# Vapeix_mini_Shield.net
KiCad netlist of a schematic drawn in Altium Designer
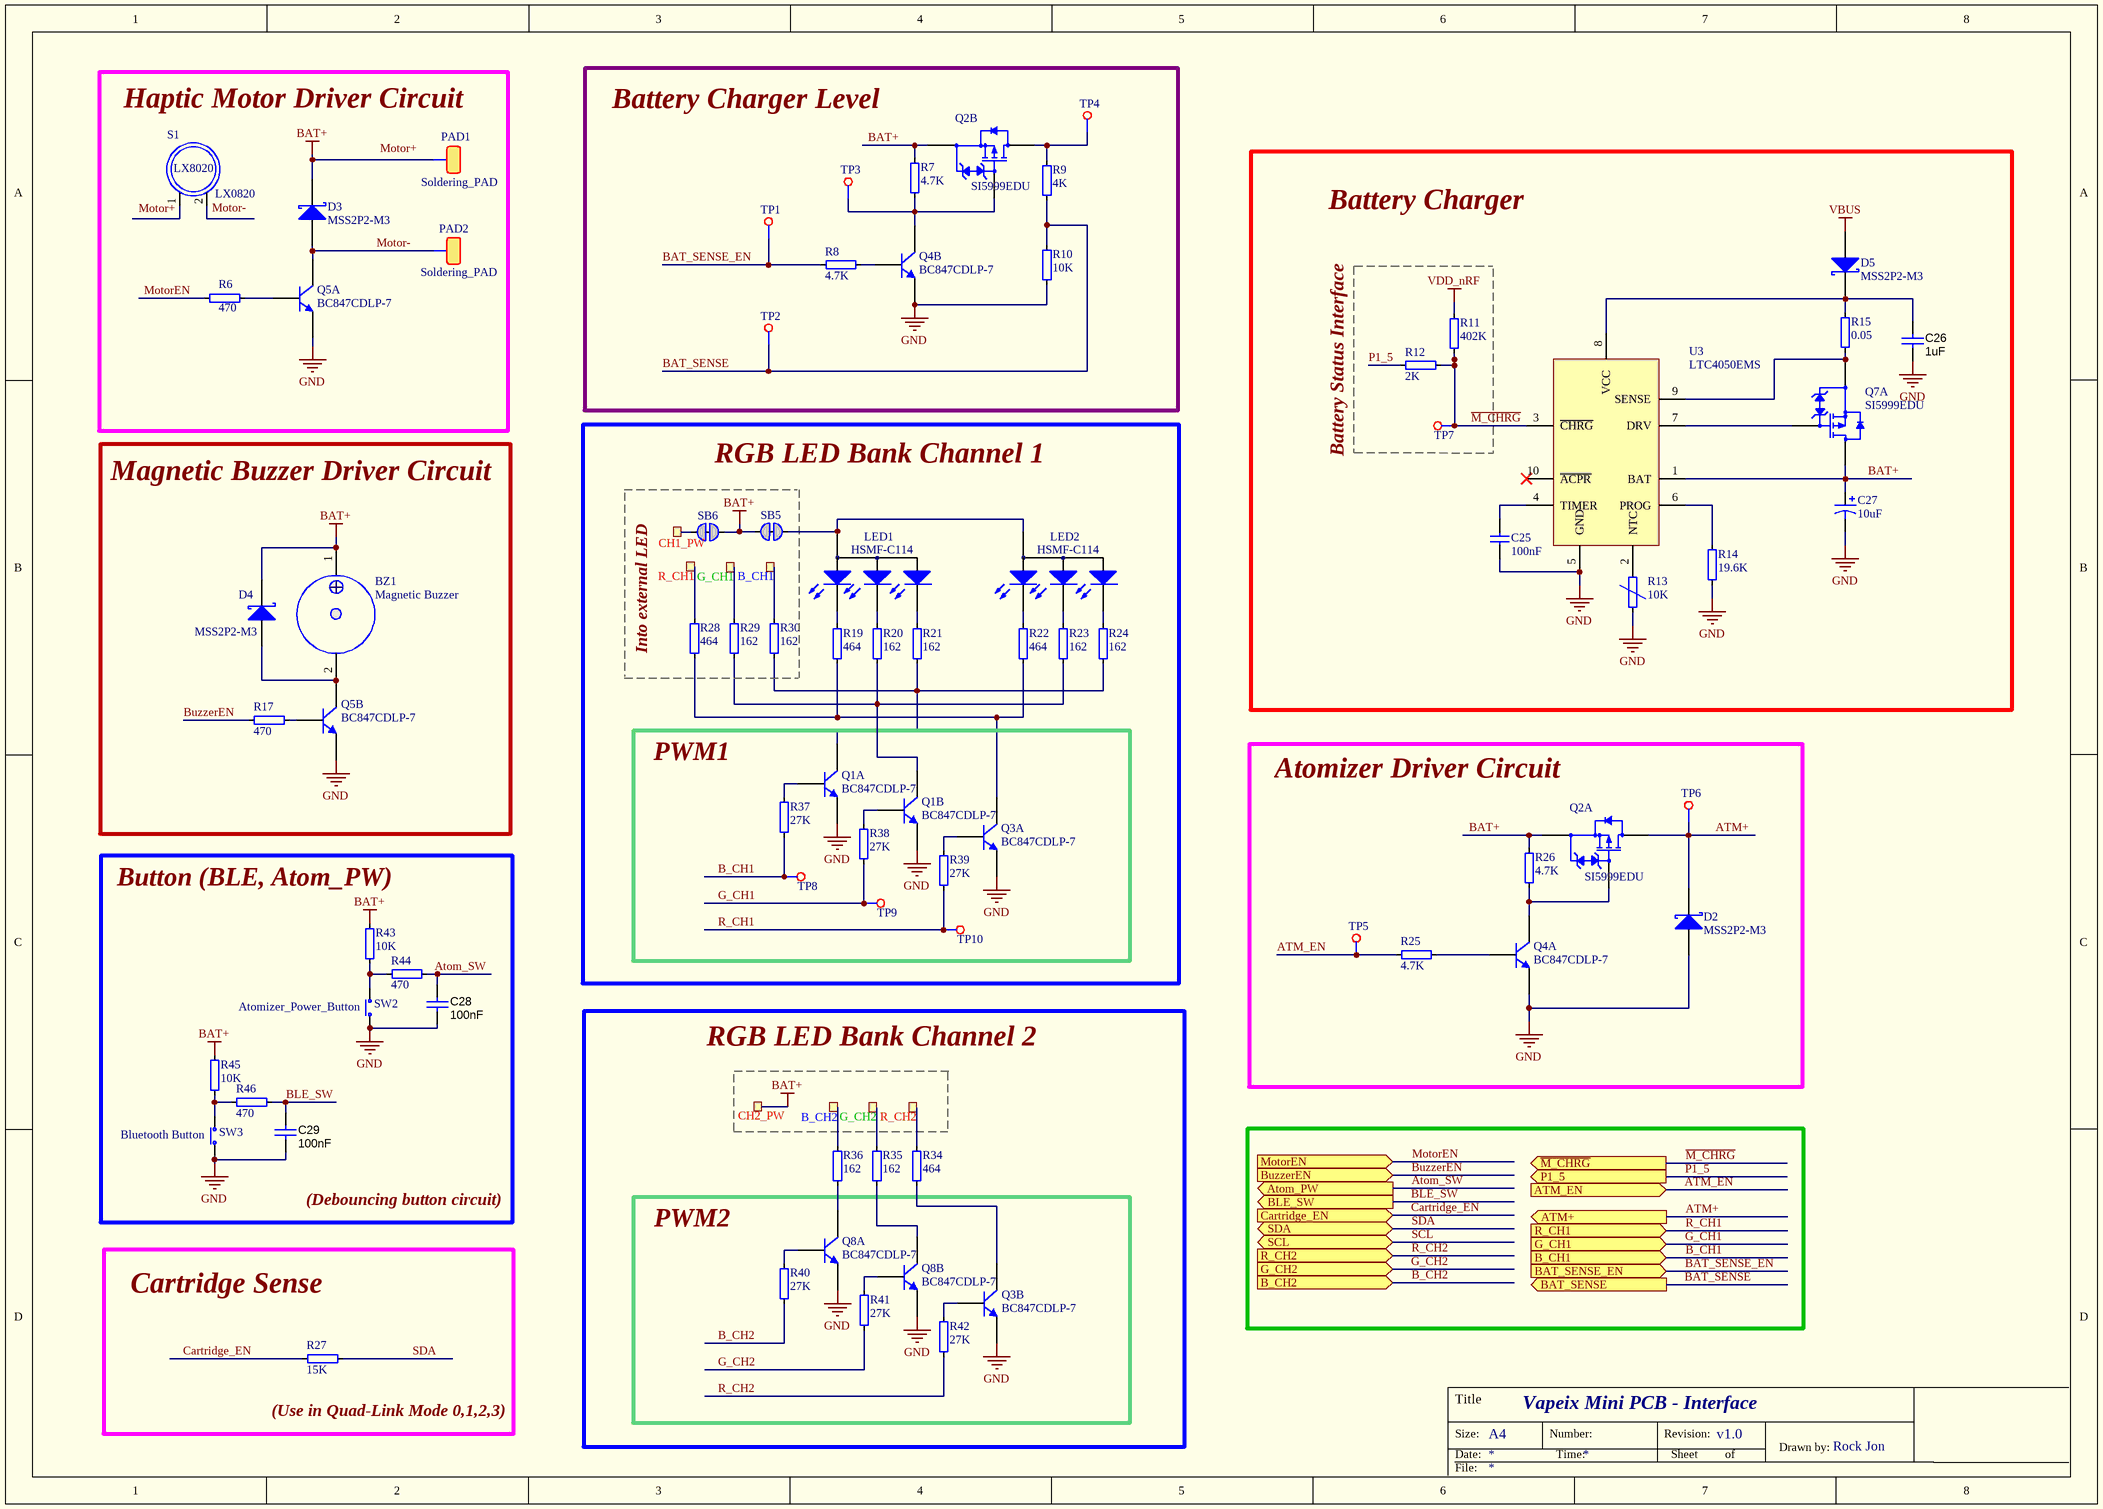
[diagram p0: Vapeix_mini_Shield.SchDoc]

(export (version "E")
  (design (tool "Eeschema 10.0.6"))
  (components
    (comp (ref "BZ1")
      (value "Magnetic Buzzer")
      (footprint "Magnetic Buzzer")
      (libsource (lib "VapeixS_LIB") (part "Magnetic Buzzer"))
    )
    (comp (ref "B_CH1")
      (value "TP")
      (footprint "TESTPAD-TH")
      (description "Testpoint, through hole")
      (fields (field (name "PART NUMBER") "Testpoint TH") (field (name "PUBLISHER") "Nordic Semiconductor"))
      (libsource (lib "pca10040") (part "TESTPAD_TH"))
    )
    (comp (ref "B_CH2")
      (value "TP")
      (footprint "TESTPAD-TH")
      (description "Testpoint, through hole")
      (fields (field (name "PART NUMBER") "Testpoint TH") (field (name "PUBLISHER") "Nordic Semiconductor"))
      (libsource (lib "pca10040") (part "TESTPAD_TH"))
    )
    (comp (ref "C25")
      (value "100nF")
      (footprint "C0201")
      (description "Capacitor, X7R, ±10%")
      (fields (field (name "PART NUMBER") "C0402-100n") (field (name "PUBLISHER") "Nordic Semiconductor"))
      (libsource (lib "Nordic Passive DB") (part "CAP"))
    )
    (comp (ref "C26")
      (value "~")
      (footprint "C0201")
      (description "CAP, CERM, 10 µF, 10 V, +/- 10%, X5R, 0805")
      (fields
        (field (name "PARTNUMBER") "GRM219R61A106KE44D")
        (field (name "VALUEDISPLAYED") "1uF")
        (field (name "MANUFACTURER") "MuRata")
        (field (name "PUBLISHER") "Texas Instruments")
      )
      (libsource (lib "Capacitor_Ceramic") (part "GRM219R61A106KE44D"))
    )
    (comp (ref "C27")
      (value "10uF")
      (footprint "CAPC1005X04L")
      (description "Polarized Capacitor (Surface Mount)")
      (fields (field (name "Comment") "Cap Pol3") (field (name "PUBLISHER") "Altium Limited"))
      (libsource (lib "Miscellaneous Devices") (part "Cap Pol3"))
    )
    (comp (ref "C28")
      (value "~")
      (footprint "C0201")
      (description "CAP, CERM, 10 µF, 10 V, +/- 10%, X5R, 0805")
      (fields
        (field (name "PARTNUMBER") "GRM219R61A106KE44D")
        (field (name "VALUEDISPLAYED") "100nF")
        (field (name "MANUFACTURER") "MuRata")
        (field (name "PUBLISHER") "Texas Instruments")
      )
      (libsource (lib "Capacitor_Ceramic") (part "GRM219R61A106KE44D"))
    )
    (comp (ref "C29")
      (value "~")
      (footprint "C0201")
      (description "CAP, CERM, 10 µF, 10 V, +/- 10%, X5R, 0805")
      (fields
        (field (name "PARTNUMBER") "GRM219R61A106KE44D")
        (field (name "VALUEDISPLAYED") "100nF")
        (field (name "MANUFACTURER") "MuRata")
        (field (name "PUBLISHER") "Texas Instruments")
      )
      (libsource (lib "Capacitor_Ceramic") (part "GRM219R61A106KE44D"))
    )
    (comp (ref "CH1_PW")
      (value "TP")
      (footprint "TESTPAD-TH")
      (description "Testpoint, through hole")
      (fields (field (name "PART NUMBER") "Testpoint TH") (field (name "PUBLISHER") "Nordic Semiconductor"))
      (libsource (lib "pca10040") (part "TESTPAD_TH"))
    )
    (comp (ref "CH2_PW")
      (value "TP")
      (footprint "TESTPAD-TH")
      (description "Testpoint, through hole")
      (fields (field (name "PART NUMBER") "Testpoint TH") (field (name "PUBLISHER") "Nordic Semiconductor"))
      (libsource (lib "pca10040") (part "TESTPAD_TH"))
    )
    (comp (ref "D2")
      (value "MSS2P2-M3")
      (footprint "MSS2P2-M3")
      (description "DIODE SCHOTTKY 20V 2A MICROSMP")
      (fields
        (field (name "MANUFACTURER") "Vishay Semiconductor Diodes Division")
        (field (name "MANUFACTURER PART NUMBER") "MSS2P2-M3/89A")
      )
      (libsource (lib "VapeixS_LIB") (part "MSS2P2-M3/89A"))
    )
    (comp (ref "D3")
      (value "MSS2P2-M3")
      (footprint "MSS2P2-M3")
      (description "DIODE SCHOTTKY 20V 2A MICROSMP")
      (fields
        (field (name "MANUFACTURER") "Vishay Semiconductor Diodes Division")
        (field (name "MANUFACTURER PART NUMBER") "MSS2P2-M3/89A")
      )
      (libsource (lib "VapeixS_LIB") (part "MSS2P2-M3/89A"))
    )
    (comp (ref "D4")
      (value "MSS2P2-M3")
      (footprint "MSS2P2-M3")
      (description "DIODE SCHOTTKY 20V 2A MICROSMP")
      (fields
        (field (name "MANUFACTURER") "Vishay Semiconductor Diodes Division")
        (field (name "MANUFACTURER PART NUMBER") "MSS2P2-M3/89A")
      )
      (libsource (lib "VapeixS_LIB") (part "MSS2P2-M3/89A"))
    )
    (comp (ref "D5")
      (value "MSS2P2-M3")
      (footprint "MSS2P2-M3")
      (description "DIODE SCHOTTKY 20V 2A MICROSMP")
      (fields
        (field (name "MANUFACTURER") "Vishay Semiconductor Diodes Division")
        (field (name "MANUFACTURER PART NUMBER") "MSS2P2-M3/89A")
      )
      (libsource (lib "VapeixS_LIB") (part "MSS2P2-M3/89A"))
    )
    (comp (ref "G_CH1")
      (value "TP")
      (footprint "TESTPAD-TH")
      (description "Testpoint, through hole")
      (fields (field (name "PART NUMBER") "Testpoint TH") (field (name "PUBLISHER") "Nordic Semiconductor"))
      (libsource (lib "pca10040") (part "TESTPAD_TH"))
    )
    (comp (ref "G_CH2")
      (value "TP")
      (footprint "TESTPAD-TH")
      (description "Testpoint, through hole")
      (fields (field (name "PART NUMBER") "Testpoint TH") (field (name "PUBLISHER") "Nordic Semiconductor"))
      (libsource (lib "pca10040") (part "TESTPAD_TH"))
    )
    (comp (ref "LED1")
      (value "HSMF-C114")
      (footprint "HSMF-C114")
      (description "LED RGB DIFFUSED 0606 SMD")
      (fields (field (name "MANUFACTURER") "Broadcom Limited"))
      (libsource (lib "VapeixS_LIB") (part "HSMF-C114"))
    )
    (comp (ref "LED2")
      (value "HSMF-C114")
      (footprint "HSMF-C114")
      (description "LED RGB DIFFUSED 0606 SMD")
      (fields (field (name "MANUFACTURER") "Broadcom Limited"))
      (libsource (lib "VapeixS_LIB") (part "HSMF-C114"))
    )
    (comp (ref "PAD1")
      (value "Soldering_PAD")
      (footprint "Soldering_PAD")
      (description "Soldering PAD")
      (libsource (lib "VapeixS_LIB") (part "Soldering_PAD"))
    )
    (comp (ref "PAD2")
      (value "Soldering_PAD")
      (footprint "Soldering_PAD")
      (description "Soldering PAD")
      (libsource (lib "VapeixS_LIB") (part "Soldering_PAD"))
    )
    (comp (ref "Q1")
      (value "BC847CDLP-7")
      (footprint "BC847CDLP-7")
      (description "TRANS 2NPN 45V 0.1A 6DFN")
      (fields (field (name "MANUFACTURER") "Diodes Incorporated"))
      (libsource (lib "") (part "BC847CDLP-7_1"))
    )
    (comp (ref "Q2")
      (value "SI5999EDU")
      (footprint "SI5999EDU")
      (description "MOSFET 2P-CH 20V 6A POWERPAK")
      (fields
        (field (name "MANUFACTURER") "Vishay Siliconix")
        (field (name "MANUFACTURER PART NUMBER") "SI5999EDU-T1-GE3")
      )
      (libsource (lib "") (part "SI5999EDU-T1-GE3_1"))
    )
    (comp (ref "Q3")
      (value "BC847CDLP-7")
      (footprint "BC847CDLP-7")
      (description "TRANS 2NPN 45V 0.1A 6DFN")
      (fields (field (name "MANUFACTURER") "Diodes Incorporated"))
      (libsource (lib "VapeixS_LIB") (part "BC847CDLP-7"))
    )
    (comp (ref "Q4")
      (value "BC847CDLP-7")
      (footprint "BC847CDLP-7")
      (description "TRANS 2NPN 45V 0.1A 6DFN")
      (fields (field (name "MANUFACTURER") "Diodes Incorporated"))
      (libsource (lib "") (part "BC847CDLP-7_2"))
    )
    (comp (ref "Q5")
      (value "BC847CDLP-7")
      (footprint "BC847CDLP-7")
      (description "TRANS 2NPN 45V 0.1A 6DFN")
      (fields (field (name "MANUFACTURER") "Diodes Incorporated"))
      (libsource (lib "") (part "BC847CDLP-7_1"))
    )
    (comp (ref "Q7")
      (value "SI5999EDU")
      (footprint "SI5999EDU")
      (description "MOSFET 2P-CH 20V 6A POWERPAK")
      (fields
        (field (name "MANUFACTURER") "Vishay Siliconix")
        (field (name "MANUFACTURER PART NUMBER") "SI5999EDU-T1-GE3")
      )
      (libsource (lib "VapeixS_LIB") (part "SI5999EDU-T1-GE3"))
    )
    (comp (ref "Q8")
      (value "BC847CDLP-7")
      (footprint "BC847CDLP-7")
      (description "TRANS 2NPN 45V 0.1A 6DFN")
      (fields (field (name "MANUFACTURER") "Diodes Incorporated"))
      (libsource (lib "VapeixS_LIB") (part "BC847CDLP-7"))
    )
    (comp (ref "R6")
      (value "470")
      (footprint "R0201")
      (description "Resistor, ±1%, 0.063W")
      (fields (field (name "PART NUMBER") "R0402-10k") (field (name "PUBLISHER") "Nordic Semiconductor"))
      (libsource (lib "Nordic Passive DB") (part "RES_1"))
    )
    (comp (ref "R7")
      (value "4.7K")
      (footprint "R0201")
      (description "Resistor, ±1%, 0.063W")
      (fields (field (name "PART NUMBER") "R0402-10k") (field (name "PUBLISHER") "Nordic Semiconductor"))
      (libsource (lib "Nordic Passive DB") (part "RES_1"))
    )
    (comp (ref "R8")
      (value "4.7K")
      (footprint "R0201")
      (description "Resistor, ±1%, 0.063W")
      (fields (field (name "PART NUMBER") "R0402-10k") (field (name "PUBLISHER") "Nordic Semiconductor"))
      (libsource (lib "Nordic Passive DB") (part "RES_1"))
    )
    (comp (ref "R9")
      (value "4K")
      (footprint "R0201")
      (description "Resistor, ±1%, 0.063W")
      (fields (field (name "PART NUMBER") "R0402-10k") (field (name "PUBLISHER") "Nordic Semiconductor"))
      (libsource (lib "Nordic Passive DB") (part "RES_1"))
    )
    (comp (ref "R10")
      (value "10K")
      (footprint "R0201")
      (description "Resistor, ±1%, 0.063W")
      (fields (field (name "PART NUMBER") "R0402-10k") (field (name "PUBLISHER") "Nordic Semiconductor"))
      (libsource (lib "Nordic Passive DB") (part "RES_1"))
    )
    (comp (ref "R11")
      (value "402K")
      (footprint "R0201")
      (description "Resistor, ±1%, 0.063W")
      (fields (field (name "PART NUMBER") "R0402-10k") (field (name "PUBLISHER") "Nordic Semiconductor"))
      (libsource (lib "Nordic Passive DB") (part "RES_1"))
    )
    (comp (ref "R12")
      (value "2K")
      (footprint "R0201")
      (description "Resistor, ±1%, 0.063W")
      (fields (field (name "PART NUMBER") "R0402-10k") (field (name "PUBLISHER") "Nordic Semiconductor"))
      (libsource (lib "Nordic Passive DB") (part "RES_1"))
    )
    (comp (ref "R13")
      (value "10K")
      (footprint "RL0503-5820-97-MS")
      (description "THERMISTOR MINI-SENS NTC 10K OHM")
      (fields
        (field (name "MANUFACTURER") "Amphenol Advanced Sensors")
        (field (name "MANUFACTURER PART NUMBER") "RL0503-5820-97-MS")
      )
      (libsource (lib "VapeixS_LIB") (part "RL0503-5820-97-MS"))
    )
    (comp (ref "R14")
      (value "19.6K")
      (footprint "R0201")
      (description "Resistor, ±1%, 0.063W")
      (fields (field (name "PART NUMBER") "R0402-10k") (field (name "PUBLISHER") "Nordic Semiconductor"))
      (libsource (lib "Nordic Passive DB") (part "RES_1"))
    )
    (comp (ref "R15")
      (value "0.05")
      (footprint "R0402")
      (description "Resistor, ±1%, 0.063W")
      (fields (field (name "PART NUMBER") "R0402-10k") (field (name "PUBLISHER") "Nordic Semiconductor"))
      (libsource (lib "Nordic Passive DB") (part "RES_1"))
    )
    (comp (ref "R17")
      (value "470")
      (footprint "RESC1005X04L")
      (description "Resistor, ±1%, 0.063W")
      (fields (field (name "PART NUMBER") "R0402-10k") (field (name "PUBLISHER") "Nordic Semiconductor"))
      (libsource (lib "Nordic Passive DB") (part "RES_1"))
    )
    (comp (ref "R19")
      (value "464")
      (footprint "R0201")
      (description "Resistor, ±1%, 0.063W")
      (fields (field (name "PART NUMBER") "R0402-10k") (field (name "PUBLISHER") "Nordic Semiconductor"))
      (libsource (lib "Nordic Passive DB") (part "RES_1"))
    )
    (comp (ref "R20")
      (value "162")
      (footprint "R0201")
      (description "Resistor, ±1%, 0.063W")
      (fields (field (name "PART NUMBER") "R0402-10k") (field (name "PUBLISHER") "Nordic Semiconductor"))
      (libsource (lib "Nordic Passive DB") (part "RES_1"))
    )
    (comp (ref "R21")
      (value "162")
      (footprint "R0201")
      (description "Resistor, ±1%, 0.063W")
      (fields (field (name "PART NUMBER") "R0402-10k") (field (name "PUBLISHER") "Nordic Semiconductor"))
      (libsource (lib "Nordic Passive DB") (part "RES_1"))
    )
    (comp (ref "R22")
      (value "464")
      (footprint "R0201")
      (description "Resistor, ±1%, 0.063W")
      (fields (field (name "PART NUMBER") "R0402-10k") (field (name "PUBLISHER") "Nordic Semiconductor"))
      (libsource (lib "Nordic Passive DB") (part "RES_1"))
    )
    (comp (ref "R23")
      (value "162")
      (footprint "R0201")
      (description "Resistor, ±1%, 0.063W")
      (fields (field (name "PART NUMBER") "R0402-10k") (field (name "PUBLISHER") "Nordic Semiconductor"))
      (libsource (lib "Nordic Passive DB") (part "RES_1"))
    )
    (comp (ref "R24")
      (value "162")
      (footprint "R0201")
      (description "Resistor, ±1%, 0.063W")
      (fields (field (name "PART NUMBER") "R0402-10k") (field (name "PUBLISHER") "Nordic Semiconductor"))
      (libsource (lib "Nordic Passive DB") (part "RES_1"))
    )
    (comp (ref "R25")
      (value "4.7K")
      (footprint "R0201")
      (description "Resistor, ±1%, 0.063W")
      (fields (field (name "PART NUMBER") "R0402-10k") (field (name "PUBLISHER") "Nordic Semiconductor"))
      (libsource (lib "Nordic Passive DB") (part "RES_1"))
    )
    (comp (ref "R26")
      (value "4.7K")
      (footprint "R0201")
      (description "Resistor, ±1%, 0.063W")
      (fields (field (name "PART NUMBER") "R0402-10k") (field (name "PUBLISHER") "Nordic Semiconductor"))
      (libsource (lib "Nordic Passive DB") (part "RES_1"))
    )
    (comp (ref "R27")
      (value "15K")
      (footprint "R0201")
      (description "Resistor, ±1%, 0.063W")
      (fields (field (name "PART NUMBER") "R0402-10k") (field (name "PUBLISHER") "Nordic Semiconductor"))
      (libsource (lib "Nordic Passive DB") (part "RES_1"))
    )
    (comp (ref "R28")
      (value "464")
      (footprint "R0201")
      (description "Resistor, ±1%, 0.063W")
      (fields (field (name "PART NUMBER") "R0402-10k") (field (name "PUBLISHER") "Nordic Semiconductor"))
      (libsource (lib "Nordic Passive DB") (part "RES_1"))
    )
    (comp (ref "R29")
      (value "162")
      (footprint "R0201")
      (description "Resistor, ±1%, 0.063W")
      (fields (field (name "PART NUMBER") "R0402-10k") (field (name "PUBLISHER") "Nordic Semiconductor"))
      (libsource (lib "Nordic Passive DB") (part "RES_1"))
    )
    (comp (ref "R30")
      (value "162")
      (footprint "R0201")
      (description "Resistor, ±1%, 0.063W")
      (fields (field (name "PART NUMBER") "R0402-10k") (field (name "PUBLISHER") "Nordic Semiconductor"))
      (libsource (lib "Nordic Passive DB") (part "RES_1"))
    )
    (comp (ref "R34")
      (value "464")
      (footprint "R0201")
      (description "Resistor, ±1%, 0.063W")
      (fields (field (name "PART NUMBER") "R0402-10k") (field (name "PUBLISHER") "Nordic Semiconductor"))
      (libsource (lib "Nordic Passive DB") (part "RES_1"))
    )
    (comp (ref "R35")
      (value "162")
      (footprint "R0201")
      (description "Resistor, ±1%, 0.063W")
      (fields (field (name "PART NUMBER") "R0402-10k") (field (name "PUBLISHER") "Nordic Semiconductor"))
      (libsource (lib "Nordic Passive DB") (part "RES_1"))
    )
    (comp (ref "R36")
      (value "162")
      (footprint "R0201")
      (description "Resistor, ±1%, 0.063W")
      (fields (field (name "PART NUMBER") "R0402-10k") (field (name "PUBLISHER") "Nordic Semiconductor"))
      (libsource (lib "Nordic Passive DB") (part "RES_1"))
    )
    (comp (ref "R37")
      (value "27K")
      (footprint "R0201")
      (description "Resistor, ±1%, 0.063W")
      (fields (field (name "PART NUMBER") "R0402-10k") (field (name "PUBLISHER") "Nordic Semiconductor"))
      (libsource (lib "Nordic Passive DB") (part "RES_1"))
    )
    (comp (ref "R38")
      (value "27K")
      (footprint "R0201")
      (description "Resistor, ±1%, 0.063W")
      (fields (field (name "PART NUMBER") "R0402-10k") (field (name "PUBLISHER") "Nordic Semiconductor"))
      (libsource (lib "Nordic Passive DB") (part "RES_1"))
    )
    (comp (ref "R39")
      (value "27K")
      (footprint "R0201")
      (description "Resistor, ±1%, 0.063W")
      (fields (field (name "PART NUMBER") "R0402-10k") (field (name "PUBLISHER") "Nordic Semiconductor"))
      (libsource (lib "Nordic Passive DB") (part "RES_1"))
    )
    (comp (ref "R40")
      (value "27K")
      (footprint "R0201")
      (description "Resistor, ±1%, 0.063W")
      (fields (field (name "PART NUMBER") "R0402-10k") (field (name "PUBLISHER") "Nordic Semiconductor"))
      (libsource (lib "Nordic Passive DB") (part "RES_1"))
    )
    (comp (ref "R41")
      (value "27K")
      (footprint "R0201")
      (description "Resistor, ±1%, 0.063W")
      (fields (field (name "PART NUMBER") "R0402-10k") (field (name "PUBLISHER") "Nordic Semiconductor"))
      (libsource (lib "Nordic Passive DB") (part "RES_1"))
    )
    (comp (ref "R42")
      (value "27K")
      (footprint "R0201")
      (description "Resistor, ±1%, 0.063W")
      (fields (field (name "PART NUMBER") "R0402-10k") (field (name "PUBLISHER") "Nordic Semiconductor"))
      (libsource (lib "Nordic Passive DB") (part "RES_1"))
    )
    (comp (ref "R43")
      (value "10K")
      (footprint "R0201")
      (description "Resistor, ±1%, 0.063W")
      (fields (field (name "PART NUMBER") "R0402-10k") (field (name "PUBLISHER") "Nordic Semiconductor"))
      (libsource (lib "Nordic Passive DB") (part "RES_1"))
    )
    (comp (ref "R44")
      (value "470")
      (footprint "R0201")
      (description "Resistor, ±1%, 0.063W")
      (fields (field (name "PART NUMBER") "R0402-10k") (field (name "PUBLISHER") "Nordic Semiconductor"))
      (libsource (lib "Nordic Passive DB") (part "RES_1"))
    )
    (comp (ref "R45")
      (value "10K")
      (footprint "R0201")
      (description "Resistor, ±1%, 0.063W")
      (fields (field (name "PART NUMBER") "R0402-10k") (field (name "PUBLISHER") "Nordic Semiconductor"))
      (libsource (lib "Nordic Passive DB") (part "RES_1"))
    )
    (comp (ref "R46")
      (value "470")
      (footprint "R0201")
      (description "Resistor, ±1%, 0.063W")
      (fields (field (name "PART NUMBER") "R0402-10k") (field (name "PUBLISHER") "Nordic Semiconductor"))
      (libsource (lib "Nordic Passive DB") (part "RES_1"))
    )
    (comp (ref "R_CH1")
      (value "TP")
      (footprint "TESTPAD-TH")
      (description "Testpoint, through hole")
      (fields (field (name "PART NUMBER") "Testpoint TH") (field (name "PUBLISHER") "Nordic Semiconductor"))
      (libsource (lib "pca10040") (part "TESTPAD_TH"))
    )
    (comp (ref "R_CH2")
      (value "TP")
      (footprint "TESTPAD-TH")
      (description "Testpoint, through hole")
      (fields (field (name "PART NUMBER") "Testpoint TH") (field (name "PUBLISHER") "Nordic Semiconductor"))
      (libsource (lib "pca10040") (part "TESTPAD_TH"))
    )
    (comp (ref "S1")
      (value "LX0820")
      (footprint "LX0820L20140926-01")
      (description "Coin Vibration Motor")
      (libsource (lib "VapeixS_LIB") (part "LX0820"))
    )
    (comp (ref "SB5")
      (value "Solderbridge")
      (footprint "Solderbridge_Shorted")
      (description "Shorted Solderbridge")
      (fields
        (field (name "PART NUMBER") "Solderbridge Shorted")
        (field (name "PUBLISHER") "Nordic Semiconductor")
      )
      (libsource (lib "Nordic Passive DB") (part "SOLDERBRIDGE_SHORTED"))
    )
    (comp (ref "SB6")
      (value "Solderbridge")
      (footprint "Solderbridge_Shorted")
      (description "Shorted Solderbridge")
      (fields
        (field (name "PART NUMBER") "Solderbridge Shorted")
        (field (name "PUBLISHER") "Nordic Semiconductor")
      )
      (libsource (lib "Nordic Passive DB") (part "SOLDERBRIDGE_SHORTED"))
    )
    (comp (ref "SW2")
      (value "Atomizer_Power_Button")
      (footprint "ALPS_SKHUxxx010_WO_GND")
      (description "ALPS - SKHUALE010 - Tactile Switch, SPNO, SMD, 6.5x6.2x2.5mm")
      (fields
        (field (name "PART NUMBER") "ALPS_SKHUALE010")
        (field (name "MANUFACTURER") "Alps")
        (field (name "PUBLISHER") "Nordic Semiconductor")
      )
      (libsource (lib "Nordic Discrete DB") (part "SW-PB"))
    )
    (comp (ref "SW3")
      (value "Bluetooth Button")
      (footprint "ALPS_SKHUxxx010_WO_GND")
      (description "ALPS - SKHUALE010 - Tactile Switch, SPNO, SMD, 6.5x6.2x2.5mm")
      (fields
        (field (name "PART NUMBER") "ALPS_SKHUALE010")
        (field (name "MANUFACTURER") "Alps")
        (field (name "PUBLISHER") "Nordic Semiconductor")
      )
      (libsource (lib "Nordic Discrete DB") (part "SW-PB"))
    )
    (comp (ref "TP1")
      (value "TP")
      (footprint "TP")
      (description "TEST POINT")
      (libsource (lib "") (part "TP_1"))
    )
    (comp (ref "TP2")
      (value "TP")
      (footprint "TP")
      (description "TEST POINT")
      (libsource (lib "") (part "TP_1"))
    )
    (comp (ref "TP3")
      (value "TP")
      (footprint "TP")
      (description "TEST POINT")
      (libsource (lib "") (part "TP_1"))
    )
    (comp (ref "TP4")
      (value "TP")
      (footprint "TP")
      (description "TEST POINT")
      (libsource (lib "") (part "TP_1"))
    )
    (comp (ref "TP5")
      (value "TP")
      (footprint "TP")
      (description "TEST POINT")
      (libsource (lib "") (part "TP_3"))
    )
    (comp (ref "TP6")
      (value "TP")
      (footprint "TP")
      (description "TEST POINT")
      (libsource (lib "") (part "TP_3"))
    )
    (comp (ref "TP7")
      (value "TP")
      (footprint "TP")
      (description "TEST POINT")
      (libsource (lib "") (part "TP_2"))
    )
    (comp (ref "TP8")
      (value "TP")
      (footprint "TP")
      (description "TEST POINT")
      (libsource (lib "VapeixS_LIB") (part "TP"))
    )
    (comp (ref "TP9")
      (value "TP")
      (footprint "TP")
      (description "TEST POINT")
      (libsource (lib "VapeixS_LIB") (part "TP"))
    )
    (comp (ref "TP10")
      (value "TP")
      (footprint "TP")
      (description "TEST POINT")
      (libsource (lib "VapeixS_LIB") (part "TP"))
    )
    (comp (ref "U3")
      (value "LTC4050EMS")
      (footprint "LTC4050EMS")
      (description "IC BATT CHRG CNTRL LI-ION 10MSOP")
      (fields
        (field (name "MANUFACTURER") "Linear Technology")
        (field (name "MANUFACTURER PART NUMBER") "LTC4050EMS-4.1#PBF")
      )
      (libsource (lib "VapeixS_LIB") (part "LTC4050EMS-4.1#PBF"))
    )
  )
  (nets
    (net (code "4") (name "/ATM+") (class "Default")
      (node (ref "D2") (pin "2") (pinfunction "K_2") (pintype "passive"))
      (node (ref "Q2") (pin "7") (pinfunction "D1_7") (pintype "passive"))
      (node (ref "TP6") (pin "1") (pinfunction "TP_1") (pintype "passive"))
    )
    (net (code "5") (name "/ATM_EN") (class "Default")
      (node (ref "R25") (pin "1") (pinfunction "1_1") (pintype "passive"))
      (node (ref "TP5") (pin "1") (pinfunction "TP_1") (pintype "passive"))
    )
    (net (code "6") (name "/Atom_SW") (class "Default")
      (node (ref "C28") (pin "1") (pinfunction "1_1") (pintype "passive"))
      (node (ref "R44") (pin "1") (pinfunction "1_1") (pintype "passive"))
    )
    (net (code "8") (name "/BAT_SENSE") (class "Default")
      (node (ref "R10") (pin "1") (pinfunction "1_1") (pintype "passive"))
      (node (ref "R9") (pin "2") (pinfunction "2_2") (pintype "passive"))
      (node (ref "TP2") (pin "1") (pinfunction "TP_1") (pintype "passive"))
    )
    (net (code "9") (name "/BAT_SENSE_EN") (class "Default")
      (node (ref "R8") (pin "2") (pinfunction "2_2") (pintype "passive"))
      (node (ref "TP1") (pin "1") (pinfunction "TP_1") (pintype "passive"))
    )
    (net (code "10") (name "/BLE_SW") (class "Default")
      (node (ref "C29") (pin "1") (pinfunction "1_1") (pintype "passive"))
      (node (ref "R46") (pin "1") (pinfunction "1_1") (pintype "passive"))
    )
    (net (code "11") (name "/B_CH1") (class "Default")
      (node (ref "R37") (pin "2") (pinfunction "2_2") (pintype "passive"))
      (node (ref "TP8") (pin "1") (pinfunction "TP_1") (pintype "passive"))
    )
    (net (code "12") (name "/B_CH2") (class "Default")
      (node (ref "R40") (pin "2") (pinfunction "2_2") (pintype "passive"))
    )
    (net (code "17") (name "/BuzzerEN") (class "Default")
      (node (ref "R17") (pin "2") (pinfunction "2_2") (pintype "passive"))
    )
    (net (code "19") (name "/Cartridge_EN") (class "Default")
      (node (ref "R27") (pin "2") (pinfunction "2_2") (pintype "passive"))
    )
    (net (code "20") (name "/G_CH1") (class "Default")
      (node (ref "R38") (pin "2") (pinfunction "2_2") (pintype "passive"))
      (node (ref "TP9") (pin "1") (pinfunction "TP_1") (pintype "passive"))
    )
    (net (code "21") (name "/G_CH2") (class "Default")
      (node (ref "R41") (pin "2") (pinfunction "2_2") (pintype "passive"))
    )
    (net (code "26") (name "/Motor-") (class "Default")
      (node (ref "D3") (pin "1") (pinfunction "A_1") (pintype "passive"))
      (node (ref "PAD2") (pin "1") (pinfunction "TP_1") (pintype "passive"))
      (node (ref "Q5") (pin "3") (pinfunction "C1_3") (pintype "passive"))
    )
    (net (code "27") (name "/MotorEN") (class "Default")
      (node (ref "R6") (pin "2") (pinfunction "2_2") (pintype "passive"))
    )
    (net (code "28") (name "/P1_5") (class "Default")
      (node (ref "R12") (pin "1") (pinfunction "1_1") (pintype "passive"))
    )
    (net (code "33") (name "/R_CH1") (class "Default")
      (node (ref "R39") (pin "2") (pinfunction "2_2") (pintype "passive"))
      (node (ref "TP10") (pin "1") (pinfunction "TP_1") (pintype "passive"))
    )
    (net (code "34") (name "/R_CH2") (class "Default")
      (node (ref "R42") (pin "1") (pinfunction "1_1") (pintype "passive"))
    )
    (net (code "36") (name "/SDA") (class "Default")
      (node (ref "R27") (pin "1") (pinfunction "1_1") (pintype "passive"))
    )
    (net (code "37") (name "/~{M_CHRG}") (class "Default")
      (node (ref "R11") (pin "2") (pinfunction "2_2") (pintype "passive"))
      (node (ref "R12") (pin "2") (pinfunction "2_2") (pintype "passive"))
      (node (ref "TP7") (pin "1") (pinfunction "TP_1") (pintype "passive"))
      (node (ref "U3") (pin "3") (pinfunction "~{CHRG}_3") (pintype "passive"))
    )
    (net (code "38") (name "BAT+") (class "Default")
      (node (ref "BZ1") (pin "1") (pinfunction "P_1") (pintype "passive"))
      (node (ref "C27") (pin "1") (pinfunction "1_1") (pintype "passive"))
      (node (ref "CH2_PW") (pin "1") (pinfunction "1_1") (pintype "passive"))
      (node (ref "D3") (pin "2") (pinfunction "K_2") (pintype "passive"))
      (node (ref "D4") (pin "2") (pinfunction "K_2") (pintype "passive"))
      (node (ref "PAD1") (pin "1") (pinfunction "TP_1") (pintype "passive"))
      (node (ref "Q2") (pin "1") (pinfunction "S1_1") (pintype "passive"))
      (node (ref "Q2") (pin "3") (pinfunction "S2_3") (pintype "passive"))
      (node (ref "Q7") (pin "7") (pinfunction "D1_7") (pintype "passive"))
      (node (ref "R26") (pin "2") (pinfunction "2_2") (pintype "passive"))
      (node (ref "R43") (pin "2") (pinfunction "2_2") (pintype "passive"))
      (node (ref "R45") (pin "2") (pinfunction "2_2") (pintype "passive"))
      (node (ref "R7") (pin "1") (pinfunction "1_1") (pintype "passive"))
      (node (ref "SB5") (pin "2") (pinfunction "1_2") (pintype "passive"))
      (node (ref "SB6") (pin "2") (pinfunction "1_2") (pintype "passive"))
      (node (ref "U3") (pin "1") (pinfunction "BAT_1") (pintype "passive"))
    )
    (net (code "39") (name "GND") (class "Default")
      (node (ref "C25") (pin "2") (pinfunction "2_2") (pintype "passive"))
      (node (ref "C26") (pin "2") (pinfunction "2_2") (pintype "passive"))
      (node (ref "C27") (pin "2") (pinfunction "2_2") (pintype "passive"))
      (node (ref "C28") (pin "2") (pinfunction "2_2") (pintype "passive"))
      (node (ref "C29") (pin "2") (pinfunction "2_2") (pintype "passive"))
      (node (ref "D2") (pin "1") (pinfunction "A_1") (pintype "passive"))
      (node (ref "Q1") (pin "1") (pinfunction "E1_1") (pintype "passive"))
      (node (ref "Q1") (pin "4") (pinfunction "E2_4") (pintype "passive"))
      (node (ref "Q3") (pin "1") (pinfunction "E1_1") (pintype "passive"))
      (node (ref "Q3") (pin "4") (pinfunction "E2_4") (pintype "passive"))
      (node (ref "Q4") (pin "1") (pinfunction "E1_1") (pintype "passive"))
      (node (ref "Q4") (pin "4") (pinfunction "E2_4") (pintype "passive"))
      (node (ref "Q5") (pin "1") (pinfunction "E1_1") (pintype "passive"))
      (node (ref "Q5") (pin "4") (pinfunction "E2_4") (pintype "passive"))
      (node (ref "Q8") (pin "1") (pinfunction "E1_1") (pintype "passive"))
      (node (ref "Q8") (pin "4") (pinfunction "E2_4") (pintype "passive"))
      (node (ref "R10") (pin "2") (pinfunction "2_2") (pintype "passive"))
      (node (ref "R13") (pin "2") (pinfunction "2_2") (pintype "passive"))
      (node (ref "R14") (pin "2") (pinfunction "2_2") (pintype "passive"))
      (node (ref "SW2") (pin "1") (pinfunction "N.O_1") (pintype "passive"))
      (node (ref "SW3") (pin "1") (pinfunction "N.O_1") (pintype "passive"))
      (node (ref "U3") (pin "5") (pinfunction "GND_5") (pintype "passive"))
    )
    (net (code "40") (name "Net-(BZ1-M)") (class "Default")
      (node (ref "BZ1") (pin "2") (pinfunction "M_2") (pintype "passive"))
      (node (ref "D4") (pin "1") (pinfunction "A_1") (pintype "passive"))
      (node (ref "Q5") (pin "6") (pinfunction "C2_6") (pintype "passive"))
    )
    (net (code "41") (name "Net-(B_CH1-Pad1)") (class "Default")
      (node (ref "B_CH1") (pin "1") (pinfunction "1_1") (pintype "passive"))
      (node (ref "R30") (pin "1") (pinfunction "1_1") (pintype "passive"))
    )
    (net (code "42") (name "Net-(B_CH2-Pad1)") (class "Default")
      (node (ref "B_CH2") (pin "1") (pinfunction "1_1") (pintype "passive"))
      (node (ref "R36") (pin "1") (pinfunction "1_1") (pintype "passive"))
    )
    (net (code "43") (name "Net-(D5-K)") (class "Default")
      (node (ref "C26") (pin "1") (pinfunction "1_1") (pintype "passive"))
      (node (ref "D5") (pin "2") (pinfunction "K_2") (pintype "passive"))
      (node (ref "R15") (pin "1") (pinfunction "1_1") (pintype "passive"))
      (node (ref "U3") (pin "8") (pinfunction "VCC_8") (pintype "passive"))
    )
    (net (code "44") (name "Net-(G_CH1-Pad1)") (class "Default")
      (node (ref "G_CH1") (pin "1") (pinfunction "1_1") (pintype "passive"))
      (node (ref "R29") (pin "1") (pinfunction "1_1") (pintype "passive"))
    )
    (net (code "45") (name "Net-(G_CH2-Pad1)") (class "Default")
      (node (ref "G_CH2") (pin "1") (pinfunction "1_1") (pintype "passive"))
      (node (ref "R35") (pin "1") (pinfunction "1_1") (pintype "passive"))
    )
    (net (code "46") (name "Net-(LED1-ANODE)") (class "Default")
      (node (ref "LED1") (pin "1") (pinfunction "ANODE_1") (pintype "passive"))
      (node (ref "LED2") (pin "1") (pinfunction "ANODE_1") (pintype "passive"))
      (node (ref "SB5") (pin "1") (pinfunction "0_1") (pintype "passive"))
    )
    (net (code "47") (name "Net-(LED1-BLUE)") (class "Default")
      (node (ref "LED1") (pin "4") (pinfunction "BLUE_4") (pintype "passive"))
      (node (ref "R21") (pin "1") (pinfunction "1_1") (pintype "passive"))
    )
    (net (code "48") (name "Net-(LED1-GREEN)") (class "Default")
      (node (ref "LED1") (pin "3") (pinfunction "GREEN_3") (pintype "passive"))
      (node (ref "R20") (pin "1") (pinfunction "1_1") (pintype "passive"))
    )
    (net (code "49") (name "Net-(LED1-RED)") (class "Default")
      (node (ref "LED1") (pin "2") (pinfunction "RED_2") (pintype "passive"))
      (node (ref "R19") (pin "1") (pinfunction "1_1") (pintype "passive"))
    )
    (net (code "50") (name "Net-(LED2-BLUE)") (class "Default")
      (node (ref "LED2") (pin "4") (pinfunction "BLUE_4") (pintype "passive"))
      (node (ref "R24") (pin "1") (pinfunction "1_1") (pintype "passive"))
    )
    (net (code "51") (name "Net-(LED2-GREEN)") (class "Default")
      (node (ref "LED2") (pin "3") (pinfunction "GREEN_3") (pintype "passive"))
      (node (ref "R23") (pin "1") (pinfunction "1_1") (pintype "passive"))
    )
    (net (code "52") (name "Net-(LED2-RED)") (class "Default")
      (node (ref "LED2") (pin "2") (pinfunction "RED_2") (pintype "passive"))
      (node (ref "R22") (pin "1") (pinfunction "1_1") (pintype "passive"))
    )
    (net (code "53") (name "Net-(Q1A-B1)") (class "Default")
      (node (ref "Q1") (pin "2") (pinfunction "B1_2") (pintype "passive"))
      (node (ref "R37") (pin "1") (pinfunction "1_1") (pintype "passive"))
    )
    (net (code "54") (name "Net-(Q1A-C1)") (class "Default")
      (node (ref "Q1") (pin "3") (pinfunction "C1_3") (pintype "passive"))
      (node (ref "R21") (pin "2") (pinfunction "2_2") (pintype "passive"))
      (node (ref "R24") (pin "2") (pinfunction "2_2") (pintype "passive"))
      (node (ref "R30") (pin "2") (pinfunction "2_2") (pintype "passive"))
    )
    (net (code "55") (name "Net-(Q1B-B2)") (class "Default")
      (node (ref "Q1") (pin "5") (pinfunction "B2_5") (pintype "passive"))
      (node (ref "R38") (pin "1") (pinfunction "1_1") (pintype "passive"))
    )
    (net (code "56") (name "Net-(Q1B-C2)") (class "Default")
      (node (ref "Q1") (pin "6") (pinfunction "C2_6") (pintype "passive"))
      (node (ref "R20") (pin "2") (pinfunction "2_2") (pintype "passive"))
      (node (ref "R23") (pin "2") (pinfunction "2_2") (pintype "passive"))
      (node (ref "R29") (pin "2") (pinfunction "2_2") (pintype "passive"))
    )
    (net (code "57") (name "Net-(Q2A-G1)") (class "Default")
      (node (ref "Q2") (pin "2") (pinfunction "G1_2") (pintype "passive"))
      (node (ref "Q4") (pin "3") (pinfunction "C1_3") (pintype "passive"))
      (node (ref "R26") (pin "1") (pinfunction "1_1") (pintype "passive"))
    )
    (net (code "58") (name "Net-(Q2B-D2)") (class "Default")
      (node (ref "Q2") (pin "5") (pinfunction "D2_5") (pintype "passive"))
      (node (ref "R9") (pin "1") (pinfunction "1_1") (pintype "passive"))
      (node (ref "TP4") (pin "1") (pinfunction "TP_1") (pintype "passive"))
    )
    (net (code "59") (name "Net-(Q2B-G2)") (class "Default")
      (node (ref "Q2") (pin "4") (pinfunction "G2_4") (pintype "passive"))
      (node (ref "Q4") (pin "6") (pinfunction "C2_6") (pintype "passive"))
      (node (ref "R7") (pin "2") (pinfunction "2_2") (pintype "passive"))
      (node (ref "TP3") (pin "1") (pinfunction "TP_1") (pintype "passive"))
    )
    (net (code "60") (name "Net-(Q3A-B1)") (class "Default")
      (node (ref "Q3") (pin "2") (pinfunction "B1_2") (pintype "passive"))
      (node (ref "R39") (pin "1") (pinfunction "1_1") (pintype "passive"))
    )
    (net (code "61") (name "Net-(Q3A-C1)") (class "Default")
      (node (ref "Q3") (pin "3") (pinfunction "C1_3") (pintype "passive"))
      (node (ref "R19") (pin "2") (pinfunction "2_2") (pintype "passive"))
      (node (ref "R22") (pin "2") (pinfunction "2_2") (pintype "passive"))
      (node (ref "R28") (pin "2") (pinfunction "2_2") (pintype "passive"))
    )
    (net (code "62") (name "Net-(Q3B-B2)") (class "Default")
      (node (ref "Q3") (pin "5") (pinfunction "B2_5") (pintype "passive"))
      (node (ref "R42") (pin "2") (pinfunction "2_2") (pintype "passive"))
    )
    (net (code "63") (name "Net-(Q3B-C2)") (class "Default")
      (node (ref "Q3") (pin "6") (pinfunction "C2_6") (pintype "passive"))
      (node (ref "R34") (pin "2") (pinfunction "2_2") (pintype "passive"))
    )
    (net (code "64") (name "Net-(Q4A-B1)") (class "Default")
      (node (ref "Q4") (pin "2") (pinfunction "B1_2") (pintype "passive"))
      (node (ref "R25") (pin "2") (pinfunction "2_2") (pintype "passive"))
    )
    (net (code "65") (name "Net-(Q4B-B2)") (class "Default")
      (node (ref "Q4") (pin "5") (pinfunction "B2_5") (pintype "passive"))
      (node (ref "R8") (pin "1") (pinfunction "1_1") (pintype "passive"))
    )
    (net (code "66") (name "Net-(Q5A-B1)") (class "Default")
      (node (ref "Q5") (pin "2") (pinfunction "B1_2") (pintype "passive"))
      (node (ref "R6") (pin "1") (pinfunction "1_1") (pintype "passive"))
    )
    (net (code "67") (name "Net-(Q5B-B2)") (class "Default")
      (node (ref "Q5") (pin "5") (pinfunction "B2_5") (pintype "passive"))
      (node (ref "R17") (pin "1") (pinfunction "1_1") (pintype "passive"))
    )
    (net (code "68") (name "Net-(Q7A-G1)") (class "Default")
      (node (ref "Q7") (pin "2") (pinfunction "G1_2") (pintype "passive"))
      (node (ref "U3") (pin "7") (pinfunction "DRV_7") (pintype "passive"))
    )
    (net (code "69") (name "Net-(Q7A-S1)") (class "Default")
      (node (ref "Q7") (pin "1") (pinfunction "S1_1") (pintype "passive"))
      (node (ref "R15") (pin "2") (pinfunction "2_2") (pintype "passive"))
      (node (ref "U3") (pin "9") (pinfunction "SENSE_9") (pintype "passive"))
    )
    (net (code "70") (name "Net-(Q8A-B1)") (class "Default")
      (node (ref "Q8") (pin "2") (pinfunction "B1_2") (pintype "passive"))
      (node (ref "R40") (pin "1") (pinfunction "1_1") (pintype "passive"))
    )
    (net (code "71") (name "Net-(Q8A-C1)") (class "Default")
      (node (ref "Q8") (pin "3") (pinfunction "C1_3") (pintype "passive"))
      (node (ref "R36") (pin "2") (pinfunction "2_2") (pintype "passive"))
    )
    (net (code "72") (name "Net-(Q8B-B2)") (class "Default")
      (node (ref "Q8") (pin "5") (pinfunction "B2_5") (pintype "passive"))
      (node (ref "R41") (pin "1") (pinfunction "1_1") (pintype "passive"))
    )
    (net (code "73") (name "Net-(Q8B-C2)") (class "Default")
      (node (ref "Q8") (pin "6") (pinfunction "C2_6") (pintype "passive"))
      (node (ref "R35") (pin "2") (pinfunction "2_2") (pintype "passive"))
    )
    (net (code "74") (name "Net-(R28-Pad1)") (class "Default")
      (node (ref "R28") (pin "1") (pinfunction "1_1") (pintype "passive"))
      (node (ref "R_CH1") (pin "1") (pinfunction "1_1") (pintype "passive"))
    )
    (net (code "75") (name "Net-(R34-Pad1)") (class "Default")
      (node (ref "R34") (pin "1") (pinfunction "1_1") (pintype "passive"))
      (node (ref "R_CH2") (pin "1") (pinfunction "1_1") (pintype "passive"))
    )
    (net (code "76") (name "Net-(SB6-0)") (class "Default")
      (node (ref "CH1_PW") (pin "1") (pinfunction "1_1") (pintype "passive"))
      (node (ref "SB6") (pin "1") (pinfunction "0_1") (pintype "passive"))
    )
    (net (code "77") (name "Net-(SW2-COM)") (class "Default")
      (node (ref "R43") (pin "1") (pinfunction "1_1") (pintype "passive"))
      (node (ref "R44") (pin "2") (pinfunction "2_2") (pintype "passive"))
      (node (ref "SW2") (pin "2") (pinfunction "COM_2") (pintype "passive"))
    )
    (net (code "78") (name "Net-(SW3-COM)") (class "Default")
      (node (ref "R45") (pin "1") (pinfunction "1_1") (pintype "passive"))
      (node (ref "R46") (pin "2") (pinfunction "2_2") (pintype "passive"))
      (node (ref "SW3") (pin "2") (pinfunction "COM_2") (pintype "passive"))
    )
    (net (code "79") (name "Net-(U3-NTC)") (class "Default")
      (node (ref "R13") (pin "1") (pinfunction "1_1") (pintype "passive"))
      (node (ref "U3") (pin "2") (pinfunction "NTC_2") (pintype "passive"))
    )
    (net (code "80") (name "Net-(U3-PROG)") (class "Default")
      (node (ref "R14") (pin "1") (pinfunction "1_1") (pintype "passive"))
      (node (ref "U3") (pin "6") (pinfunction "PROG_6") (pintype "passive"))
    )
    (net (code "81") (name "Net-(U3-TIMER)") (class "Default")
      (node (ref "C25") (pin "1") (pinfunction "1_1") (pintype "passive"))
      (node (ref "U3") (pin "4") (pinfunction "TIMER_4") (pintype "passive"))
    )
    (net (code "82") (name "VBUS") (class "Default")
      (node (ref "D5") (pin "1") (pinfunction "A_1") (pintype "passive"))
    )
    (net (code "83") (name "VDD_nRF") (class "Default")
      (node (ref "R11") (pin "1") (pinfunction "1_1") (pintype "passive"))
    )
    (net (code "84") (name "unconnected-(S1-GND-Pad2)") (class "Default")
      (node (ref "S1") (pin "2") (pinfunction "GND_2") (pintype "passive"))
    )
    (net (code "85") (name "unconnected-(S1-PW-Pad1)") (class "Default")
      (node (ref "S1") (pin "1") (pinfunction "PW_1") (pintype "passive"))
    )
    (net (code "86") (name "unconnected-(U3-~{ACPR}-Pad10)") (class "Default")
      (node (ref "U3") (pin "10") (pinfunction "~{ACPR}_10") (pintype "passive+no_connect"))
    )
  )
)
